# Lighting.net
KiCad netlist of a schematic drawn in Altium Designer
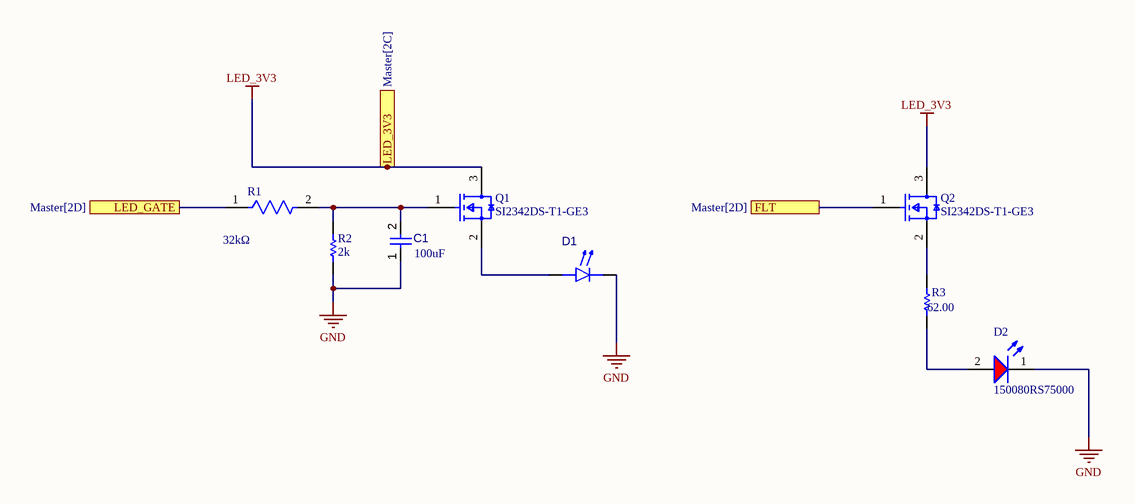
[diagram p0: Lighting.SchDoc]

(export (version "E")
  (design (tool "Eeschema 10.0.6"))
  (components
    (comp (ref "C1")
      (value "100uF")
      (footprint "CAPC3216X19N")
      (description "6.3V 100uF X5R ±10% 1206 Multilayer Ceramic Capacitors MLCC - SMD/SMT ROHS")
      (fields (field (name "Comment") "GRM31CR60J107KEA8L"))
      (libsource (lib "Brian Tan") (part "CAP-NP-2"))
    )
    (comp (ref "D1")
      (value "HL-AM-2835H489W-S1-08HL-HR3")
      (footprint "HL-AM-2835H489W-S1-08HL-HR3-Footprint-1")
      (libsource (lib "Brian Tan") (part "DIODE-LED-2"))
    )
    (comp (ref "D2")
      (value "150080RS75000")
      (footprint "WL-SMCW_0805_150080xx75000")
      (description "LED Uni-Color Red 630nm 2-Pin Chip 0805(2012Metric) T/R")
      (libsource (lib "Altium Content Vault") (part "LED_Red_2A-1K"))
    )
    (comp (ref "Q1")
      (value "SI2342DS-T1-GE3")
      (footprint "FP-S-03946-MFG")
      (description "MOSFET N-CH 8V 6A SOT-23")
      (fields
        (field (name "OCTOPART") "https://octopart.com/si2342ds-t1-ge3-vishay-45050957")
        (field (name "MANUFACTURER") "Vishay")
      )
      (libsource (lib "Altium Content Vault") (part "1661867509f36a4ffa577829538a895"))
    )
    (comp (ref "Q2")
      (value "SI2342DS-T1-GE3")
      (footprint "FP-S-03946-MFG")
      (description "MOSFET N-CH 8V 6A SOT-23")
      (fields
        (field (name "OCTOPART") "https://octopart.com/si2342ds-t1-ge3-vishay-45050957")
        (field (name "MANUFACTURER") "Vishay")
      )
      (libsource (lib "Altium Content Vault") (part "1661867509f36a4ffa577829538a895"))
    )
    (comp (ref "R1")
      (value "RT0603BRD0732KL")
      (footprint "FP-RT0603-0_55-MFG")
      (description "RT0603BRD0732KL High Precision-High Stability Chip Resistor Thin Film 0603 32kOhm 0.1% Paper T/R")
      (fields (field (name "RESISTANCE") "32kΩ") (field (name "TOLERANCE") "0.1%"))
      (libsource (lib "Altium Content Vault") (part "1029c3af85768c4190bb7ad29bc67b5"))
    )
    (comp (ref "R2")
      (value "2k")
      (footprint "RESC1608X55X30ML15T15")
      (fields (field (name "PART NUMBER") "ERJ-3EKF2001V") (field (name "MANUFACTURER") "Panasonic"))
      (libsource (lib "Altium Content Vault") (part "RES"))
    )
    (comp (ref "R3")
      (value "62.00")
      (footprint "RESC1206(3216)_N")
      (description "62R 0.25W 1% 1206 (3216 Metric)  SMD")
      (fields (field (name "POWER") "0.25 W") (field (name "TOLERANCE") "1 %"))
      (libsource (lib "Altium Content Vault") (part "RES"))
    )
  )
  (nets
    (net (code "1") (name "/FLT") (class "Default")
      (node (ref "Q2") (pin "1") (pinfunction "G_1") (pintype "passive"))
    )
    (net (code "2") (name "/LED_GATE") (class "Default")
      (node (ref "R1") (pin "1") (pinfunction "1_1") (pintype "passive"))
    )
    (net (code "3") (name "GND") (class "Default")
      (node (ref "C1") (pin "1") (pinfunction "1_1") (pintype "passive"))
      (node (ref "D1") (pin "1") (pinfunction "K_1") (pintype "passive"))
      (node (ref "D2") (pin "1") (pinfunction "K_1") (pintype "passive"))
      (node (ref "R2") (pin "1") (pinfunction "1_1") (pintype "passive"))
    )
    (net (code "4") (name "LED_3V3") (class "Default")
      (node (ref "Q1") (pin "3") (pinfunction "D_3") (pintype "passive"))
      (node (ref "Q2") (pin "3") (pinfunction "D_3") (pintype "passive"))
    )
    (net (code "5") (name "Net-(D1-A)") (class "Default")
      (node (ref "D1") (pin "2") (pinfunction "A_2") (pintype "passive"))
      (node (ref "Q1") (pin "2") (pinfunction "S_2") (pintype "passive"))
    )
    (net (code "6") (name "Net-(D2-A)") (class "Default")
      (node (ref "D2") (pin "2") (pinfunction "A_2") (pintype "passive"))
      (node (ref "R3") (pin "2") (pinfunction "2_2") (pintype "passive"))
    )
    (net (code "7") (name "Net-(Q1-G)") (class "Default")
      (node (ref "C1") (pin "2") (pinfunction "2_2") (pintype "passive"))
      (node (ref "Q1") (pin "1") (pinfunction "G_1") (pintype "passive"))
      (node (ref "R1") (pin "2") (pinfunction "2_2") (pintype "passive"))
      (node (ref "R2") (pin "2") (pinfunction "2_2") (pintype "passive"))
    )
    (net (code "8") (name "Net-(Q2-S)") (class "Default")
      (node (ref "Q2") (pin "2") (pinfunction "S_2") (pintype "passive"))
      (node (ref "R3") (pin "1") (pinfunction "1_1") (pintype "passive"))
    )
  )
)
